# Connectors.net
KiCad netlist of a schematic drawn in Altium Designer
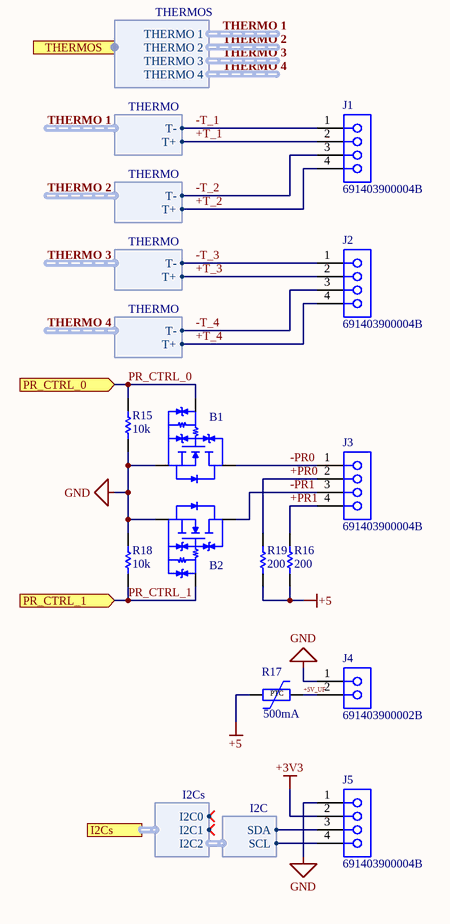
[diagram p0: Connectors.SchDoc]

(export (version "E")
  (design (tool "Eeschema 10.0.6"))
  (components
    (comp (ref "B1")
      (value "CMP-532-000000-3")
      (footprint "SOTFL95P240X88-3N")
      (description "Trans MOSFET N-CH Si 60V 0.65A Automotive 3-Pin SOT-23F T/R")
      (libsource (lib "IIT Motorsports") (part "CMP-532-000000-3"))
    )
    (comp (ref "B2")
      (value "CMP-532-000000-3")
      (footprint "SOTFL95P240X88-3N")
      (description "Trans MOSFET N-CH Si 60V 0.65A Automotive 3-Pin SOT-23F T/R")
      (libsource (lib "IIT Motorsports") (part "CMP-532-000000-3"))
    )
    (comp (ref "J1")
      (value "691403900004B")
      (footprint "691403900004B")
      (description "Barrier Strip Terminal Block")
      (libsource (lib "IIT Motorsports") (part "CMP-002-00140-1"))
    )
    (comp (ref "J2")
      (value "691403900004B")
      (footprint "691403900004B")
      (description "Barrier Strip Terminal Block")
      (libsource (lib "IIT Motorsports") (part "CMP-002-00140-1"))
    )
    (comp (ref "J3")
      (value "691403900004B")
      (footprint "691403900004B")
      (description "Barrier Strip Terminal Block")
      (libsource (lib "IIT Motorsports") (part "CMP-002-00140-1"))
    )
    (comp (ref "J4")
      (value "691403900002B")
      (footprint "691403900002B")
      (description "Barrier Strip Terminal Block")
      (libsource (lib "IIT Motorsports") (part "CMP-002-00139-1"))
    )
    (comp (ref "J5")
      (value "691403900004B")
      (footprint "691403900004B")
      (description "Barrier Strip Terminal Block")
      (libsource (lib "IIT Motorsports") (part "CMP-002-00140-1"))
    )
    (comp (ref "R15")
      (value "10k")
      (footprint "RES 0805_2012")
      (fields
        (field (name "TOLERANCE") "1%")
        (field (name "POWER") "125mW")
        (field (name "Comment") "CRCW080510K0FKEAC")
      )
      (libsource (lib "IIT Motorsports") (part "RES"))
    )
    (comp (ref "R16")
      (value "200")
      (footprint "RES 1206_3216")
      (description "Res Thin Film 1206 200 Ohm 0.1% 1/4W ±25ppm/°C Molded SMD SMD Punched Carrier T/R")
      (fields (field (name "TOLERANCE") "0.1%") (field (name "POWER") "250mW"))
      (libsource (lib "IIT Motorsports") (part "RES"))
    )
    (comp (ref "R17")
      (value "CMP-009-00302-6")
      (footprint "RESC3216X125N")
      (description "PTC Resettable Fuse, 24V, 0.15ohm, Surface Mount")
      (fields (field (name "MP") "0ZCJ0050AF2E") (field (name "MF") "{'manufacturer': u'Bel Fuse'}"))
      (libsource (lib "IIT Motorsports") (part "CMP-009-00302-6"))
    )
    (comp (ref "R18")
      (value "10k")
      (footprint "RES 0805_2012")
      (fields
        (field (name "TOLERANCE") "1%")
        (field (name "POWER") "125mW")
        (field (name "Comment") "CRCW080510K0FKEAC")
      )
      (libsource (lib "IIT Motorsports") (part "RES"))
    )
    (comp (ref "R19")
      (value "200")
      (footprint "RES 1206_3216")
      (description "Res Thin Film 1206 200 Ohm 0.1% 1/4W ±25ppm/°C Molded SMD SMD Punched Carrier T/R")
      (fields (field (name "TOLERANCE") "0.1%") (field (name "POWER") "250mW"))
      (libsource (lib "IIT Motorsports") (part "RES"))
    )
  )
  (nets
    (net (code "7") (name "+3V3") (class "Default")
      (node (ref "J5") (pin "2") (pinfunction "2_2") (pintype "passive"))
    )
    (net (code "8") (name "+5") (class "Default")
      (node (ref "R16") (pin "1") (pinfunction "1_1") (pintype "passive"))
      (node (ref "R17") (pin "1") (pinfunction "1_1") (pintype "passive"))
      (node (ref "R19") (pin "1") (pinfunction "1_1") (pintype "passive"))
    )
    (net (code "9") (name "/+5V_UF") (class "Default")
      (node (ref "J4") (pin "2") (pinfunction "2_2") (pintype "passive"))
      (node (ref "R17") (pin "2") (pinfunction "2_2") (pintype "passive"))
    )
    (net (code "10") (name "/+PR0") (class "Default")
      (node (ref "J3") (pin "2") (pinfunction "2_2") (pintype "passive"))
      (node (ref "R19") (pin "2") (pinfunction "2_2") (pintype "passive"))
    )
    (net (code "11") (name "/+PR1") (class "Default")
      (node (ref "J3") (pin "4") (pinfunction "4_4") (pintype "passive"))
      (node (ref "R16") (pin "2") (pinfunction "2_2") (pintype "passive"))
    )
    (net (code "12") (name "/+T_1") (class "Default")
      (node (ref "J1") (pin "2") (pinfunction "2_2") (pintype "passive"))
    )
    (net (code "13") (name "/+T_2") (class "Default")
      (node (ref "J1") (pin "4") (pinfunction "4_4") (pintype "passive"))
    )
    (net (code "14") (name "/+T_3") (class "Default")
      (node (ref "J2") (pin "2") (pinfunction "2_2") (pintype "passive"))
    )
    (net (code "15") (name "/+T_4") (class "Default")
      (node (ref "J2") (pin "4") (pinfunction "4_4") (pintype "passive"))
    )
    (net (code "16") (name "/-PR0") (class "Default")
      (node (ref "B1") (pin "3") (pinfunction "D_3") (pintype "passive"))
      (node (ref "J3") (pin "1") (pinfunction "1_1") (pintype "passive"))
    )
    (net (code "17") (name "/-PR1") (class "Default")
      (node (ref "B2") (pin "3") (pinfunction "D_3") (pintype "passive"))
      (node (ref "J3") (pin "3") (pinfunction "3_3") (pintype "passive"))
    )
    (net (code "18") (name "/-T_1") (class "Default")
      (node (ref "J1") (pin "1") (pinfunction "1_1") (pintype "passive"))
    )
    (net (code "19") (name "/-T_2") (class "Default")
      (node (ref "J1") (pin "3") (pinfunction "3_3") (pintype "passive"))
    )
    (net (code "20") (name "/-T_3") (class "Default")
      (node (ref "J2") (pin "1") (pinfunction "1_1") (pintype "passive"))
    )
    (net (code "21") (name "/-T_4") (class "Default")
      (node (ref "J2") (pin "3") (pinfunction "3_3") (pintype "passive"))
    )
    (net (code "23") (name "/PR_CTRL_0") (class "Default")
      (node (ref "B1") (pin "1") (pinfunction "G_1") (pintype "passive"))
      (node (ref "R15") (pin "2") (pinfunction "2_2") (pintype "passive"))
    )
    (net (code "24") (name "/PR_CTRL_1") (class "Default")
      (node (ref "B2") (pin "1") (pinfunction "G_1") (pintype "passive"))
      (node (ref "R18") (pin "1") (pinfunction "1_1") (pintype "passive"))
    )
    (net (code "25") (name "/SCL") (class "Default")
      (node (ref "J5") (pin "4") (pinfunction "4_4") (pintype "passive"))
    )
    (net (code "26") (name "/SDA") (class "Default")
      (node (ref "J5") (pin "3") (pinfunction "3_3") (pintype "passive"))
    )
    (net (code "36") (name "GND") (class "Default")
      (node (ref "B1") (pin "2") (pinfunction "S_2") (pintype "passive"))
      (node (ref "B2") (pin "2") (pinfunction "S_2") (pintype "passive"))
      (node (ref "J4") (pin "1") (pinfunction "1_1") (pintype "passive"))
      (node (ref "J5") (pin "1") (pinfunction "1_1") (pintype "passive"))
      (node (ref "R15") (pin "1") (pinfunction "1_1") (pintype "passive"))
      (node (ref "R18") (pin "2") (pinfunction "2_2") (pintype "passive"))
    )
  )
)
